# TensoStudent.net
KiCad netlist of a schematic drawn in Altium Designer
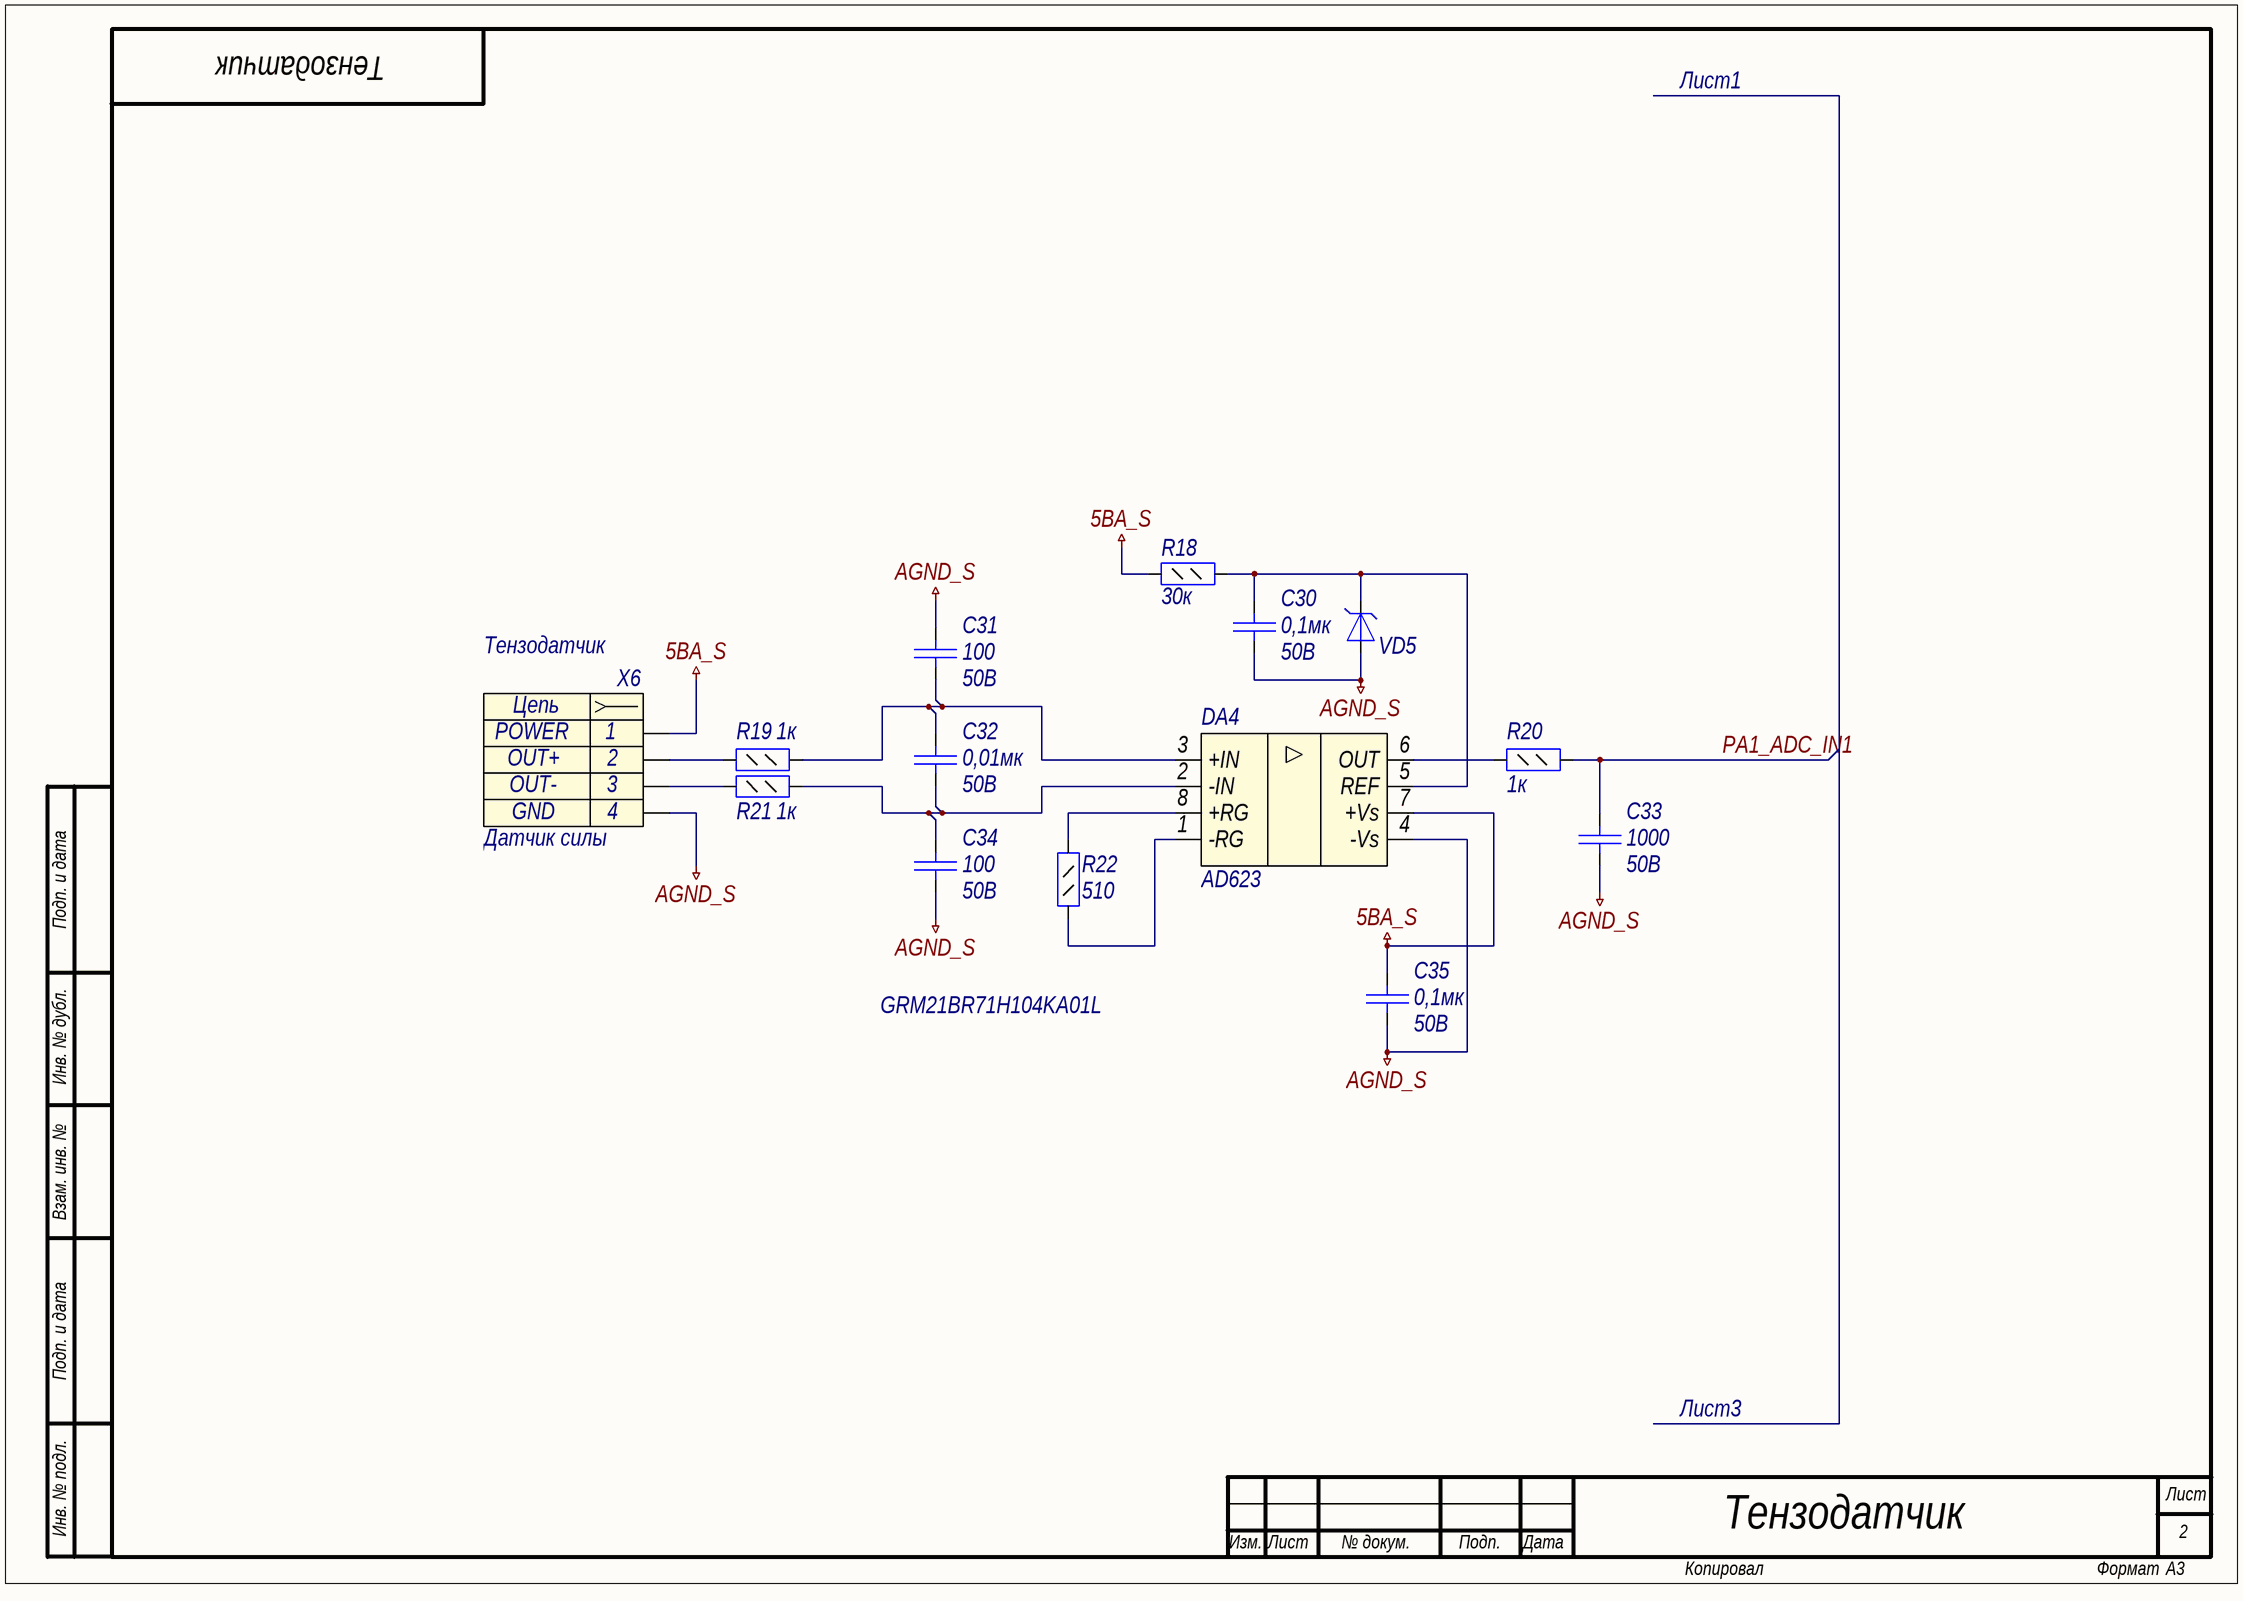
[diagram p0: TensoStudent.SchDoc]

(export (version "E")
  (design (tool "Eeschema 10.0.6"))
  (components
    (comp (ref "C30")
      (value "0,1мк")
      (footprint "C0805")
      (description "Конденсатор")
      (fields
        (field (name "VOLTAGE") "50В")
        (field (name "PART NUMBER") "GRM21BR71H104KA01L ")
        (field (name "Comment") "Capacitor")
      )
      (libsource (lib "MOP44") (part "Capacitor"))
    )
    (comp (ref "C31")
      (value "100")
      (footprint "C0603")
      (description "Конденсатор")
      (fields
        (field (name "VOLTAGE") "50B")
        (field (name "PART NUMBER") "GRM1885C1H101J")
        (field (name "Comment") "Capacitor")
      )
      (libsource (lib "MOP44") (part "Capacitor"))
    )
    (comp (ref "C32")
      (value "0,01мк")
      (footprint "C0805")
      (description "Конденсатор")
      (fields
        (field (name "VOLTAGE") "50B")
        (field (name "PART NUMBER") "GRM216R71H103K")
        (field (name "Comment") "Capacitor")
      )
      (libsource (lib "MOP44") (part "Capacitor"))
    )
    (comp (ref "C33")
      (value "1000")
      (footprint "C0603")
      (description "Конденсатор")
      (fields
        (field (name "VOLTAGE") "50B")
        (field (name "PART NUMBER") "GRM188R71H102K")
        (field (name "Comment") "Capacitor")
      )
      (libsource (lib "MOP44") (part "Capacitor"))
    )
    (comp (ref "C34")
      (value "100")
      (footprint "C0603")
      (description "Конденсатор")
      (fields
        (field (name "VOLTAGE") "50B")
        (field (name "PART NUMBER") "GRM1885C1H101J")
        (field (name "Comment") "Capacitor")
      )
      (libsource (lib "MOP44") (part "Capacitor"))
    )
    (comp (ref "C35")
      (value "0,1мк")
      (footprint "C0805")
      (description "Конденсатор")
      (fields
        (field (name "VOLTAGE") "50В")
        (field (name "PART NUMBER") "GRM21BR71H104KA01L ")
        (field (name "Comment") "Capacitor")
      )
      (libsource (lib "MOP44") (part "Capacitor"))
    )
    (comp (ref "DA4")
      (value "AD623")
      (footprint "SO8")
      (description "Low Cost Low Power  Instrumentation Amplifier")
      (fields (field (name "PART NUMBER") "AD623ARZ"))
      (libsource (lib "MOP44") (part "AD623"))
    )
    (comp (ref "R18")
      (value "30к")
      (footprint "R0805")
      (description "Резистор")
      (fields (field (name "PART NUMBER") "RC0805FR-0730KL") (field (name "POWER") "0,125Вт"))
      (libsource (lib "") (part "Resistor_0,125Вт_1"))
    )
    (comp (ref "R19")
      (value "1к")
      (footprint "R0805")
      (description "Резистор")
      (fields (field (name "PART NUMBER") "RC0805FR-071KL") (field (name "POWER") "0,125Вт"))
      (libsource (lib "") (part "Resistor_0,125Вт_1"))
    )
    (comp (ref "R20")
      (value "1к")
      (footprint "R0805")
      (description "Резистор")
      (fields (field (name "PART NUMBER") "RC0805FR-071KL") (field (name "POWER") "0,125Вт"))
      (libsource (lib "") (part "Resistor_0,125Вт_1"))
    )
    (comp (ref "R21")
      (value "1к")
      (footprint "R0805")
      (description "Резистор")
      (fields (field (name "PART NUMBER") "RC0805FR-071KL") (field (name "POWER") "0,125Вт"))
      (libsource (lib "") (part "Resistor_0,125Вт_1"))
    )
    (comp (ref "R22")
      (value "510")
      (footprint "R0805")
      (description "Резистор")
      (fields (field (name "PART NUMBER") "RC0805FR-07510RL") (field (name "POWER") "0,125Вт"))
      (libsource (lib "MOP44") (part "Resistor_0,125Вт"))
    )
    (comp (ref "VD5")
      (value "LM4040BIM3-2.5/NOPB")
      (footprint "SOT23-3")
      (description "Прецезионный источник опорного напряжения")
      (libsource (lib "MOP44") (part "LM4040BIM3-2.5/NOPB"))
    )
    (comp (ref "X6")
      (value "Датчик силы")
      (footprint "CWF-4R")
      (description "Разъем - 4 конт. розетка")
      (fields (field (name "PART NUMBER") "DS1069-4MRW6SA"))
      (libsource (lib "MOP44") (part "Header_4_sct"))
    )
  )
  (nets
    (net (code "1") (name "/PA1_ADC_IN1") (class "Default")
      (node (ref "C33") (pin "2") (pinfunction "2_2") (pintype "passive"))
      (node (ref "R20") (pin "2") (pinfunction "2_2") (pintype "passive"))
    )
    (net (code "2") (name "5BA_S") (class "Default")
      (node (ref "C35") (pin "2") (pinfunction "2_2") (pintype "passive"))
      (node (ref "DA4") (pin "7") (pinfunction "+Vs_7") (pintype "passive"))
      (node (ref "R18") (pin "1") (pinfunction "1_1") (pintype "passive"))
      (node (ref "X6") (pin "1") (pinfunction "1_1") (pintype "passive"))
    )
    (net (code "3") (name "AGND_S") (class "Default")
      (node (ref "C30") (pin "1") (pinfunction "1_1") (pintype "passive"))
      (node (ref "C31") (pin "2") (pinfunction "2_2") (pintype "passive"))
      (node (ref "C33") (pin "1") (pinfunction "1_1") (pintype "passive"))
      (node (ref "C34") (pin "1") (pinfunction "1_1") (pintype "passive"))
      (node (ref "C35") (pin "1") (pinfunction "1_1") (pintype "passive"))
      (node (ref "DA4") (pin "4") (pinfunction "-Vs_4") (pintype "passive"))
      (node (ref "VD5") (pin "2") (pinfunction "A_2") (pintype "passive"))
      (node (ref "X6") (pin "4") (pinfunction "4_4") (pintype "passive"))
    )
    (net (code "4") (name "Net-(DA4-+IN)") (class "Default")
      (node (ref "C31") (pin "1") (pinfunction "1_1") (pintype "passive"))
      (node (ref "C32") (pin "2") (pinfunction "2_2") (pintype "passive"))
      (node (ref "DA4") (pin "3") (pinfunction "+IN_3") (pintype "passive"))
      (node (ref "R19") (pin "2") (pinfunction "2_2") (pintype "passive"))
    )
    (net (code "5") (name "Net-(DA4-+RG)") (class "Default")
      (node (ref "DA4") (pin "8") (pinfunction "+RG_8") (pintype "passive"))
      (node (ref "R22") (pin "2") (pinfunction "2_2") (pintype "passive"))
    )
    (net (code "6") (name "Net-(DA4--IN)") (class "Default")
      (node (ref "C32") (pin "1") (pinfunction "1_1") (pintype "passive"))
      (node (ref "C34") (pin "2") (pinfunction "2_2") (pintype "passive"))
      (node (ref "DA4") (pin "2") (pinfunction "-IN_2") (pintype "passive"))
      (node (ref "R21") (pin "2") (pinfunction "2_2") (pintype "passive"))
    )
    (net (code "7") (name "Net-(DA4--RG)") (class "Default")
      (node (ref "DA4") (pin "1") (pinfunction "-RG_1") (pintype "passive"))
      (node (ref "R22") (pin "1") (pinfunction "1_1") (pintype "passive"))
    )
    (net (code "8") (name "Net-(DA4-OUT)") (class "Default")
      (node (ref "DA4") (pin "6") (pinfunction "OUT_6") (pintype "passive"))
      (node (ref "R20") (pin "1") (pinfunction "1_1") (pintype "passive"))
    )
    (net (code "9") (name "Net-(DA4-REF)") (class "Default")
      (node (ref "C30") (pin "2") (pinfunction "2_2") (pintype "passive"))
      (node (ref "DA4") (pin "5") (pinfunction "REF_5") (pintype "passive"))
      (node (ref "R18") (pin "2") (pinfunction "2_2") (pintype "passive"))
      (node (ref "VD5") (pin "1") (pinfunction "K_1") (pintype "passive"))
    )
    (net (code "10") (name "Net-(R19-Pad1)") (class "Default")
      (node (ref "R19") (pin "1") (pinfunction "1_1") (pintype "passive"))
      (node (ref "X6") (pin "2") (pinfunction "2_2") (pintype "passive"))
    )
    (net (code "11") (name "Net-(R21-Pad1)") (class "Default")
      (node (ref "R21") (pin "1") (pinfunction "1_1") (pintype "passive"))
      (node (ref "X6") (pin "3") (pinfunction "3_3") (pintype "passive"))
    )
  )
)
